# Connect.net
KiCad netlist of a schematic drawn in Altium Designer
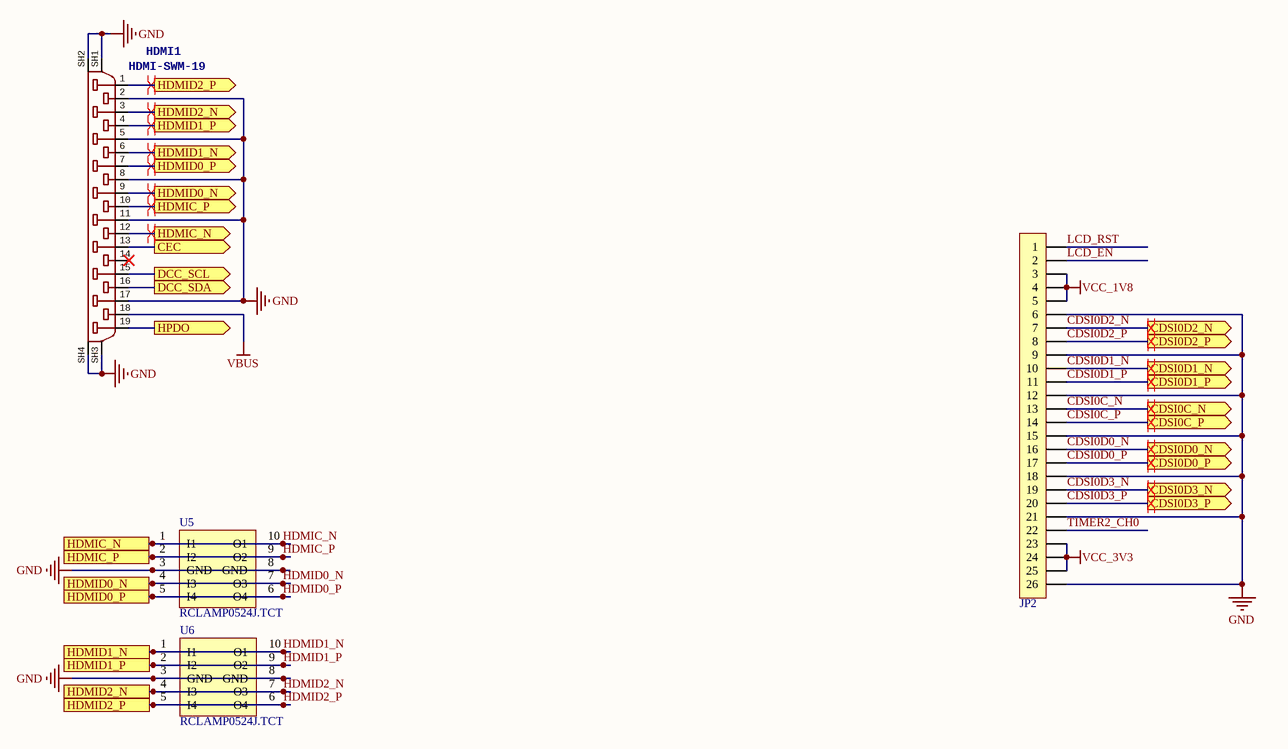
[diagram p0: Connect.SchDoc]

(export (version "E")
  (design (tool "Eeschema 10.0.6"))
  (components
    (comp (ref "HDMI1")
      (value "HDMI-SWM-19")
      (footprint "HDMI-SWM-19")
      (libsource (lib "User") (part "HDMI-MC34931HDMI-SWM-19_1"))
    )
    (comp (ref "JP2")
      (value "FPC1.0-26P")
      (footprint "FPC0.5 2H-WS-26P")
      (description "FPC连接器")
      (fields (field (name "版权归属") "源创客"))
      (libsource (lib "4.14 - FPC连接器") (part "FPC-26P"))
    )
    (comp (ref "U5")
      (value "RCLAMP0524J.TCT")
      (footprint "RCLAMP0524J.TCT")
      (description "HDMI ESD保护器件 C35368")
      (libsource (lib "User") (part "RCLAMP0524J.TCT"))
    )
    (comp (ref "U6")
      (value "RCLAMP0524J.TCT")
      (footprint "RCLAMP0524J.TCT")
      (description "HDMI ESD保护器件 C35368")
      (libsource (lib "User") (part "RCLAMP0524J.TCT"))
    )
  )
  (nets
    (net (code "1") (name "/CDSI0C_N") (class "Default")
      (node (ref "JP2") (pin "13") (pinfunction "13_13") (pintype "passive"))
    )
    (net (code "2") (name "/CDSI0C_P") (class "Default")
      (node (ref "JP2") (pin "14") (pinfunction "14_14") (pintype "passive"))
    )
    (net (code "3") (name "/CDSI0D0_N") (class "Default")
      (node (ref "JP2") (pin "16") (pinfunction "16_16") (pintype "passive"))
    )
    (net (code "4") (name "/CDSI0D0_P") (class "Default")
      (node (ref "JP2") (pin "17") (pinfunction "17_17") (pintype "passive"))
    )
    (net (code "5") (name "/CDSI0D1_N") (class "Default")
      (node (ref "JP2") (pin "10") (pinfunction "10_10") (pintype "passive"))
    )
    (net (code "6") (name "/CDSI0D1_P") (class "Default")
      (node (ref "JP2") (pin "11") (pinfunction "11_11") (pintype "passive"))
    )
    (net (code "7") (name "/CDSI0D2_N") (class "Default")
      (node (ref "JP2") (pin "7") (pinfunction "7_7") (pintype "passive"))
    )
    (net (code "8") (name "/CDSI0D2_P") (class "Default")
      (node (ref "JP2") (pin "8") (pinfunction "8_8") (pintype "passive"))
    )
    (net (code "9") (name "/CDSI0D3_N") (class "Default")
      (node (ref "JP2") (pin "19") (pinfunction "19_19") (pintype "passive"))
    )
    (net (code "10") (name "/CDSI0D3_P") (class "Default")
      (node (ref "JP2") (pin "20") (pinfunction "20_20") (pintype "passive"))
    )
    (net (code "11") (name "/CEC") (class "Default")
      (node (ref "HDMI1") (pin "13") (pinfunction "13_13") (pintype "passive"))
    )
    (net (code "12") (name "/DCC_SCL") (class "Default")
      (node (ref "HDMI1") (pin "15") (pinfunction "15_15") (pintype "passive"))
    )
    (net (code "13") (name "/DCC_SDA") (class "Default")
      (node (ref "HDMI1") (pin "16") (pinfunction "16_16") (pintype "passive"))
    )
    (net (code "14") (name "/HDMIC_N") (class "Default")
      (node (ref "HDMI1") (pin "12") (pinfunction "12_12") (pintype "passive"))
      (node (ref "U5") (pin "1") (pinfunction "I1_1") (pintype "passive"))
      (node (ref "U5") (pin "10") (pinfunction "O1_10") (pintype "passive"))
    )
    (net (code "15") (name "/HDMIC_P") (class "Default")
      (node (ref "HDMI1") (pin "10") (pinfunction "10_10") (pintype "passive"))
      (node (ref "U5") (pin "2") (pinfunction "I2_2") (pintype "passive"))
      (node (ref "U5") (pin "9") (pinfunction "O2_9") (pintype "passive"))
    )
    (net (code "16") (name "/HDMID0_N") (class "Default")
      (node (ref "HDMI1") (pin "9") (pinfunction "9_9") (pintype "passive"))
      (node (ref "U5") (pin "4") (pinfunction "I3_4") (pintype "passive"))
      (node (ref "U5") (pin "7") (pinfunction "O3_7") (pintype "passive"))
    )
    (net (code "17") (name "/HDMID0_P") (class "Default")
      (node (ref "HDMI1") (pin "7") (pinfunction "7_7") (pintype "passive"))
      (node (ref "U5") (pin "5") (pinfunction "I4_5") (pintype "passive"))
      (node (ref "U5") (pin "6") (pinfunction "O4_6") (pintype "passive"))
    )
    (net (code "18") (name "/HDMID1_N") (class "Default")
      (node (ref "HDMI1") (pin "6") (pinfunction "6_6") (pintype "passive"))
      (node (ref "U6") (pin "1") (pinfunction "I1_1") (pintype "passive"))
      (node (ref "U6") (pin "10") (pinfunction "O1_10") (pintype "passive"))
    )
    (net (code "19") (name "/HDMID1_P") (class "Default")
      (node (ref "HDMI1") (pin "4") (pinfunction "4_4") (pintype "passive"))
      (node (ref "U6") (pin "2") (pinfunction "I2_2") (pintype "passive"))
      (node (ref "U6") (pin "9") (pinfunction "O2_9") (pintype "passive"))
    )
    (net (code "20") (name "/HDMID2_N") (class "Default")
      (node (ref "HDMI1") (pin "3") (pinfunction "3_3") (pintype "passive"))
      (node (ref "U6") (pin "4") (pinfunction "I3_4") (pintype "passive"))
      (node (ref "U6") (pin "7") (pinfunction "O3_7") (pintype "passive"))
    )
    (net (code "21") (name "/HDMID2_P") (class "Default")
      (node (ref "HDMI1") (pin "1") (pinfunction "1_1") (pintype "passive"))
      (node (ref "U6") (pin "5") (pinfunction "I4_5") (pintype "passive"))
      (node (ref "U6") (pin "6") (pinfunction "O4_6") (pintype "passive"))
    )
    (net (code "22") (name "/HPDO") (class "Default")
      (node (ref "HDMI1") (pin "19") (pinfunction "19_19") (pintype "passive"))
    )
    (net (code "23") (name "/LCD_EN") (class "Default")
      (node (ref "JP2") (pin "2") (pinfunction "2_2") (pintype "passive"))
    )
    (net (code "24") (name "/LCD_RST") (class "Default")
      (node (ref "JP2") (pin "1") (pinfunction "1_1") (pintype "passive"))
    )
    (net (code "25") (name "/TIMER2_CH0") (class "Default")
      (node (ref "JP2") (pin "22") (pinfunction "22_22") (pintype "passive"))
    )
    (net (code "26") (name "GND") (class "Default")
      (node (ref "HDMI1") (pin "11") (pinfunction "11_11") (pintype "passive"))
      (node (ref "HDMI1") (pin "17") (pinfunction "17_17") (pintype "passive"))
      (node (ref "HDMI1") (pin "2") (pinfunction "2_2") (pintype "passive"))
      (node (ref "HDMI1") (pin "5") (pinfunction "5_5") (pintype "passive"))
      (node (ref "HDMI1") (pin "8") (pinfunction "8_8") (pintype "passive"))
      (node (ref "HDMI1") (pin "SH1") (pinfunction "20_SH1") (pintype "passive"))
      (node (ref "HDMI1") (pin "SH2") (pinfunction "21_SH2") (pintype "passive"))
      (node (ref "HDMI1") (pin "SH3") (pinfunction "22_SH3") (pintype "passive"))
      (node (ref "HDMI1") (pin "SH4") (pinfunction "23_SH4") (pintype "passive"))
      (node (ref "JP2") (pin "12") (pinfunction "12_12") (pintype "passive"))
      (node (ref "JP2") (pin "15") (pinfunction "15_15") (pintype "passive"))
      (node (ref "JP2") (pin "18") (pinfunction "18_18") (pintype "passive"))
      (node (ref "JP2") (pin "21") (pinfunction "21_21") (pintype "passive"))
      (node (ref "JP2") (pin "26") (pinfunction "26_26") (pintype "passive"))
      (node (ref "JP2") (pin "6") (pinfunction "6_6") (pintype "passive"))
      (node (ref "JP2") (pin "9") (pinfunction "9_9") (pintype "passive"))
      (node (ref "U5") (pin "3") (pinfunction "GND_3") (pintype "passive"))
      (node (ref "U5") (pin "8") (pinfunction "GND_8") (pintype "passive"))
      (node (ref "U6") (pin "3") (pinfunction "GND_3") (pintype "passive"))
      (node (ref "U6") (pin "8") (pinfunction "GND_8") (pintype "passive"))
    )
    (net (code "27") (name "VBUS") (class "Default")
      (node (ref "HDMI1") (pin "18") (pinfunction "18_18") (pintype "passive"))
    )
    (net (code "28") (name "VCC_1V8") (class "Default")
      (node (ref "JP2") (pin "3") (pinfunction "3_3") (pintype "passive"))
      (node (ref "JP2") (pin "4") (pinfunction "4_4") (pintype "passive"))
      (node (ref "JP2") (pin "5") (pinfunction "5_5") (pintype "passive"))
    )
    (net (code "29") (name "VCC_3V3") (class "Default")
      (node (ref "JP2") (pin "23") (pinfunction "23_23") (pintype "passive"))
      (node (ref "JP2") (pin "24") (pinfunction "24_24") (pintype "passive"))
      (node (ref "JP2") (pin "25") (pinfunction "25_25") (pintype "passive"))
    )
    (net (code "30") (name "unconnected-(HDMI1-Pad14)") (class "Default")
      (node (ref "HDMI1") (pin "14") (pinfunction "14_14") (pintype "passive+no_connect"))
    )
  )
)
